# MIC2260x_Module_Electrolytic.net
KiCad netlist of a schematic drawn in EAGLE
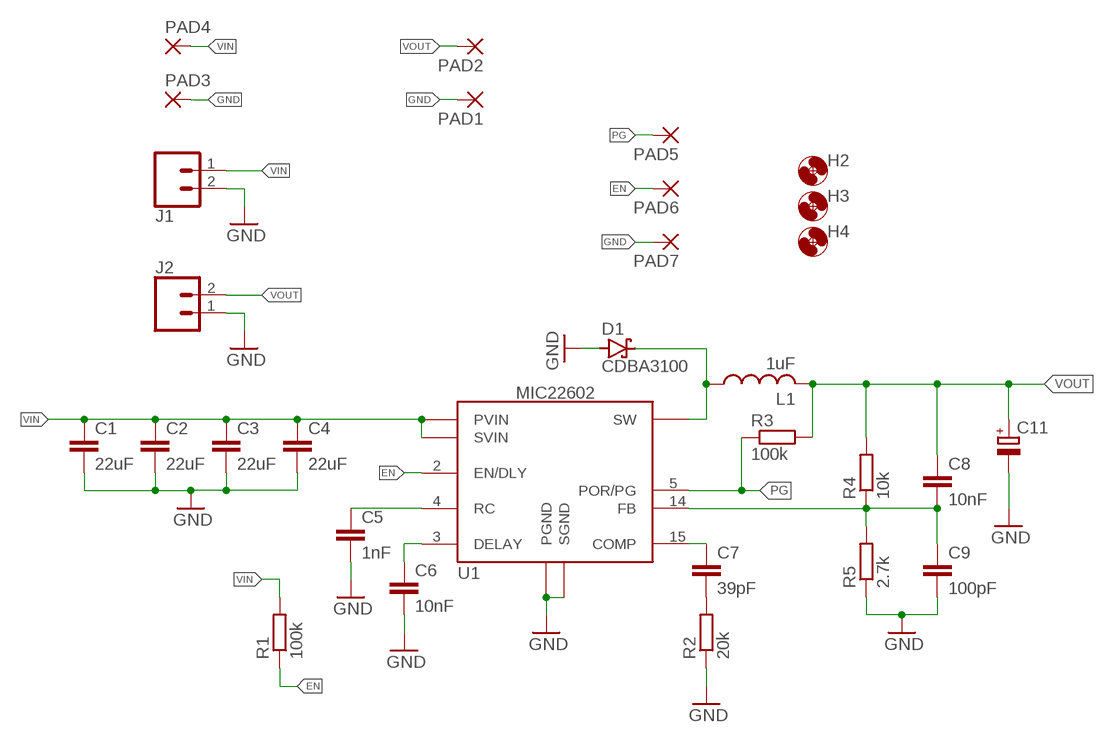
[diagram p0: schematic, sheet 1]

(export (version "E")
  (design (tool "Eeschema 10.0.6"))
  (components
    (comp (ref "C1")
      (value "22uF")
      (footprint "eagle-import:C0805")
      (fields (field (name "MF") "Murata") (field (name "MPN") "GRM219R61C226ME15L"))
      (libsource (lib "eagle-import") (part "C-EUC080522UF"))
    )
    (comp (ref "C2")
      (value "22uF")
      (footprint "eagle-import:C0805")
      (fields (field (name "MF") "Murata") (field (name "MPN") "GRM219R61C226ME15L"))
      (libsource (lib "eagle-import") (part "C-EUC080522UF"))
    )
    (comp (ref "C3")
      (value "22uF")
      (footprint "eagle-import:C0805")
      (fields (field (name "MF") "Murata") (field (name "MPN") "GRM219R61C226ME15L"))
      (libsource (lib "eagle-import") (part "C-EUC080522UF"))
    )
    (comp (ref "C4")
      (value "22uF")
      (footprint "eagle-import:C0805")
      (fields (field (name "MF") "Murata") (field (name "MPN") "GRM219R61C226ME15L"))
      (libsource (lib "eagle-import") (part "C-EUC080522UF"))
    )
    (comp (ref "C5")
      (value "1nF")
      (footprint "eagle-import:C0402")
      (libsource (lib "eagle-import") (part "C-EUC0402"))
    )
    (comp (ref "C6")
      (value "10nF")
      (footprint "eagle-import:C0402")
      (libsource (lib "eagle-import") (part "C-EUC0402"))
    )
    (comp (ref "C7")
      (value "39pF")
      (footprint "eagle-import:C0402")
      (libsource (lib "eagle-import") (part "C-EUC0402"))
    )
    (comp (ref "C8")
      (value "10nF")
      (footprint "eagle-import:C0402")
      (libsource (lib "eagle-import") (part "C-EUC0402"))
    )
    (comp (ref "C9")
      (value "100pF")
      (footprint "eagle-import:C0402")
      (libsource (lib "eagle-import") (part "C-EUC0402"))
    )
    (comp (ref "C11")
      (value "CPOL-EUUD-6,3X7,7")
      (footprint "eagle-import:UD-6,3X7,7_NICHICON")
      (libsource (lib "eagle-import") (part "CPOL-EUUD-6,3X7,7"))
    )
    (comp (ref "D1")
      (value "CDBA3100")
      (footprint "eagle-import:DO214AC")
      (libsource (lib "eagle-import") (part "DIODE_SCHOTTKYDO-214AC"))
    )
    (comp (ref "H2")
      (value "MOUNTING_HOLE4_NP")
      (footprint "eagle-import:4_40")
      (fields (field (name "MPN") "DNP"))
      (libsource (lib "eagle-import") (part "MOUNTING_HOLE4_NP"))
    )
    (comp (ref "H3")
      (value "MOUNTING_HOLE4_NP")
      (footprint "eagle-import:4_40")
      (fields (field (name "MPN") "DNP"))
      (libsource (lib "eagle-import") (part "MOUNTING_HOLE4_NP"))
    )
    (comp (ref "H4")
      (value "MOUNTING_HOLE4_NP")
      (footprint "eagle-import:4_40")
      (fields (field (name "MPN") "DNP"))
      (libsource (lib "eagle-import") (part "MOUNTING_HOLE4_NP"))
    )
    (comp (ref "J1")
      (value "CONN_023.5MM_ROUND_RESTRICT")
      (footprint "eagle-import:SCREWTERMINAL-3.5MM-2_ROUND_RESTRICT")
      (fields (field (name "MF") "On Shore") (field (name "MPN") "OSTTE020161"))
      (libsource (lib "eagle-import") (part "CONN_023.5MM_ROUND_RESTRICT"))
    )
    (comp (ref "J2")
      (value "CONN_023.5MM_ROUND_RESTRICT")
      (footprint "eagle-import:SCREWTERMINAL-3.5MM-2_ROUND_RESTRICT")
      (fields (field (name "MF") "On Shore") (field (name "MPN") "OSTTE020161"))
      (libsource (lib "eagle-import") (part "CONN_023.5MM_ROUND_RESTRICT"))
    )
    (comp (ref "L1")
      (value "1uF")
      (footprint "eagle-import:WE-MAIA(4.1X4.1)")
      (libsource (lib "eagle-import") (part "INDUCTOR_MAIA_4.1X4.1"))
    )
    (comp (ref "PAD1")
      (value "SMD5")
      (footprint "eagle-import:SMD2,54-5,08")
      (libsource (lib "eagle-import") (part "SMD5"))
    )
    (comp (ref "PAD2")
      (value "SMD5")
      (footprint "eagle-import:SMD2,54-5,08")
      (libsource (lib "eagle-import") (part "SMD5"))
    )
    (comp (ref "PAD3")
      (value "SMD5")
      (footprint "eagle-import:SMD2,54-5,08")
      (libsource (lib "eagle-import") (part "SMD5"))
    )
    (comp (ref "PAD4")
      (value "SMD5")
      (footprint "eagle-import:SMD2,54-5,08")
      (libsource (lib "eagle-import") (part "SMD5"))
    )
    (comp (ref "PAD5")
      (value "SMD2")
      (footprint "eagle-import:SMD1,27-2,54")
      (fields (field (name "MPN") "DNP"))
      (libsource (lib "eagle-import") (part "SMD2"))
    )
    (comp (ref "PAD6")
      (value "SMD2")
      (footprint "eagle-import:SMD1,27-2,54")
      (fields (field (name "MPN") "DNP"))
      (libsource (lib "eagle-import") (part "SMD2"))
    )
    (comp (ref "PAD7")
      (value "SMD2")
      (footprint "eagle-import:SMD1,27-2,54")
      (fields (field (name "MPN") "DNP"))
      (libsource (lib "eagle-import") (part "SMD2"))
    )
    (comp (ref "R1")
      (value "100k")
      (footprint "eagle-import:R0402")
      (fields (field (name "MF") "Yageo") (field (name "MPN") "RC0402FR-07100KL"))
      (libsource (lib "eagle-import") (part "R-EU_R0402100K"))
    )
    (comp (ref "R2")
      (value "20k")
      (footprint "eagle-import:R0402")
      (fields (field (name "MF") "Yageo"))
      (libsource (lib "eagle-import") (part "R-EU_R0402"))
    )
    (comp (ref "R3")
      (value "100k")
      (footprint "eagle-import:R0402")
      (fields (field (name "MF") "Yageo") (field (name "MPN") "RC0402FR-07100KL"))
      (libsource (lib "eagle-import") (part "R-EU_R0402100K"))
    )
    (comp (ref "R4")
      (value "10k")
      (footprint "eagle-import:R0402")
      (fields (field (name "MF") "Yageo") (field (name "MPN") "RC0402FR-0710KL"))
      (libsource (lib "eagle-import") (part "R-EU_R040210K"))
    )
    (comp (ref "R5")
      (value "2.7k")
      (footprint "eagle-import:R0402")
      (fields (field (name "MF") "Yageo"))
      (libsource (lib "eagle-import") (part "R-EU_R0402"))
    )
    (comp (ref "U1")
      (value "MIC22602")
      (footprint "eagle-import:QFN24_POWER")
      (fields
        (field (name "DISP") "MIC22602")
        (field (name "MF") "Microchip")
        (field (name "MPN") "MIC22602YML-TR")
      )
      (libsource (lib "eagle-import") (part "MIC22602"))
    )
  )
  (nets
    (net (code "1") (name "EN") (class "Default")
      (node (ref "PAD6") (pin "1") (pinfunction "P_1") (pintype "passive"))
      (node (ref "R1") (pin "1") (pinfunction "1_1") (pintype "passive"))
      (node (ref "U1") (pin "2") (pinfunction "EN/DLY_2") (pintype "bidirectional"))
    )
    (net (code "2") (name "GND") (class "Default")
      (node (ref "C1") (pin "2") (pinfunction "2_2") (pintype "passive"))
      (node (ref "C11") (pin "-") (pinfunction "-_-") (pintype "passive"))
      (node (ref "C2") (pin "2") (pinfunction "2_2") (pintype "passive"))
      (node (ref "C3") (pin "2") (pinfunction "2_2") (pintype "passive"))
      (node (ref "C4") (pin "2") (pinfunction "2_2") (pintype "passive"))
      (node (ref "C5") (pin "2") (pinfunction "2_2") (pintype "passive"))
      (node (ref "C6") (pin "2") (pinfunction "2_2") (pintype "passive"))
      (node (ref "C9") (pin "2") (pinfunction "2_2") (pintype "passive"))
      (node (ref "D1") (pin "A") (pinfunction "A_A") (pintype "passive"))
      (node (ref "J1") (pin "2") (pinfunction "2_2") (pintype "passive"))
      (node (ref "J2") (pin "1") (pinfunction "1_1") (pintype "passive"))
      (node (ref "PAD1") (pin "1") (pinfunction "P_1") (pintype "passive"))
      (node (ref "PAD3") (pin "1") (pinfunction "P_1") (pintype "passive"))
      (node (ref "PAD7") (pin "1") (pinfunction "P_1") (pintype "passive"))
      (node (ref "R2") (pin "1") (pinfunction "1_1") (pintype "passive"))
      (node (ref "R5") (pin "1") (pinfunction "1_1") (pintype "passive"))
      (node (ref "U1") (pin "12") (pinfunction "PGND_12") (pintype "bidirectional"))
      (node (ref "U1") (pin "16") (pinfunction "SGND_16") (pintype "bidirectional"))
      (node (ref "U1") (pin "19") (pinfunction "PGND_19") (pintype "bidirectional"))
      (node (ref "U1") (pin "24") (pinfunction "PGND_24") (pintype "bidirectional"))
      (node (ref "U1") (pin "7") (pinfunction "PGND_7") (pintype "bidirectional"))
      (node (ref "U1") (pin "EP") (pinfunction "PGND_EP") (pintype "bidirectional"))
      (node (ref "U1") (pin "EP@1") (pinfunction "PGND_EP@1") (pintype "bidirectional"))
      (node (ref "U1") (pin "EP@2") (pinfunction "PGND_EP@2") (pintype "bidirectional"))
      (node (ref "U1") (pin "EP@3") (pinfunction "PGND_EP@3") (pintype "bidirectional"))
      (node (ref "U1") (pin "EP@4") (pinfunction "PGND_EP@4") (pintype "bidirectional"))
      (node (ref "U1") (pin "EP@5") (pinfunction "PGND_EP@5") (pintype "bidirectional"))
      (node (ref "U1") (pin "EP@6") (pinfunction "PGND_EP@6") (pintype "bidirectional"))
      (node (ref "U1") (pin "EP@7") (pinfunction "PGND_EP@7") (pintype "bidirectional"))
      (node (ref "U1") (pin "EP@8") (pinfunction "PGND_EP@8") (pintype "bidirectional"))
      (node (ref "U1") (pin "EP@9") (pinfunction "PGND_EP@9") (pintype "bidirectional"))
    )
    (net (code "3") (name "Net-(C7-Pad2)") (class "Default")
      (node (ref "C7") (pin "2") (pinfunction "2_2") (pintype "passive"))
      (node (ref "R2") (pin "2") (pinfunction "2_2") (pintype "passive"))
    )
    (net (code "4") (name "Net-(L1-1)") (class "Default")
      (node (ref "D1") (pin "C") (pinfunction "C_C") (pintype "passive"))
      (node (ref "L1") (pin "P$1") (pinfunction "1_P$1") (pintype "passive"))
      (node (ref "U1") (pin "10") (pinfunction "SW_10") (pintype "bidirectional"))
      (node (ref "U1") (pin "11") (pinfunction "SW_11") (pintype "bidirectional"))
      (node (ref "U1") (pin "20") (pinfunction "SW_20") (pintype "bidirectional"))
      (node (ref "U1") (pin "21") (pinfunction "SW_21") (pintype "bidirectional"))
      (node (ref "U1") (pin "22") (pinfunction "SW_22") (pintype "bidirectional"))
      (node (ref "U1") (pin "23") (pinfunction "SW_23") (pintype "bidirectional"))
      (node (ref "U1") (pin "8") (pinfunction "SW_8") (pintype "bidirectional"))
      (node (ref "U1") (pin "9") (pinfunction "SW_9") (pintype "bidirectional"))
    )
    (net (code "5") (name "Net-(U1-COMP)") (class "Default")
      (node (ref "C7") (pin "1") (pinfunction "1_1") (pintype "passive"))
      (node (ref "U1") (pin "15") (pinfunction "COMP_15") (pintype "bidirectional"))
    )
    (net (code "6") (name "Net-(U1-DELAY)") (class "Default")
      (node (ref "C6") (pin "1") (pinfunction "1_1") (pintype "passive"))
      (node (ref "U1") (pin "3") (pinfunction "DELAY_3") (pintype "bidirectional"))
    )
    (net (code "7") (name "Net-(U1-FB)") (class "Default")
      (node (ref "C8") (pin "2") (pinfunction "2_2") (pintype "passive"))
      (node (ref "C9") (pin "1") (pinfunction "1_1") (pintype "passive"))
      (node (ref "R4") (pin "1") (pinfunction "1_1") (pintype "passive"))
      (node (ref "R5") (pin "2") (pinfunction "2_2") (pintype "passive"))
      (node (ref "U1") (pin "14") (pinfunction "FB_14") (pintype "bidirectional"))
    )
    (net (code "8") (name "Net-(U1-RC)") (class "Default")
      (node (ref "C5") (pin "1") (pinfunction "1_1") (pintype "passive"))
      (node (ref "U1") (pin "4") (pinfunction "RC_4") (pintype "bidirectional"))
    )
    (net (code "9") (name "PG") (class "Default")
      (node (ref "PAD5") (pin "1") (pinfunction "P_1") (pintype "passive"))
      (node (ref "R3") (pin "1") (pinfunction "1_1") (pintype "passive"))
      (node (ref "U1") (pin "5") (pinfunction "POR/PG_5") (pintype "bidirectional"))
    )
    (net (code "10") (name "VIN") (class "Default")
      (node (ref "C1") (pin "1") (pinfunction "1_1") (pintype "passive"))
      (node (ref "C2") (pin "1") (pinfunction "1_1") (pintype "passive"))
      (node (ref "C3") (pin "1") (pinfunction "1_1") (pintype "passive"))
      (node (ref "C4") (pin "1") (pinfunction "1_1") (pintype "passive"))
      (node (ref "J1") (pin "1") (pinfunction "1_1") (pintype "passive"))
      (node (ref "PAD4") (pin "1") (pinfunction "P_1") (pintype "passive"))
      (node (ref "R1") (pin "2") (pinfunction "2_2") (pintype "passive"))
      (node (ref "U1") (pin "1") (pinfunction "PVIN_1") (pintype "bidirectional"))
      (node (ref "U1") (pin "13") (pinfunction "PVIN_13") (pintype "bidirectional"))
      (node (ref "U1") (pin "17") (pinfunction "SVIN_17") (pintype "bidirectional"))
      (node (ref "U1") (pin "18") (pinfunction "PVIN_18") (pintype "bidirectional"))
      (node (ref "U1") (pin "6") (pinfunction "PVIN_6") (pintype "bidirectional"))
    )
    (net (code "11") (name "VOUT") (class "Default")
      (node (ref "C11") (pin "+") (pinfunction "+_+") (pintype "passive"))
      (node (ref "C8") (pin "1") (pinfunction "1_1") (pintype "passive"))
      (node (ref "J2") (pin "2") (pinfunction "2_2") (pintype "passive"))
      (node (ref "L1") (pin "P$2") (pinfunction "2_P$2") (pintype "passive"))
      (node (ref "PAD2") (pin "1") (pinfunction "P_1") (pintype "passive"))
      (node (ref "R3") (pin "2") (pinfunction "2_2") (pintype "passive"))
      (node (ref "R4") (pin "2") (pinfunction "2_2") (pintype "passive"))
    )
  )
)
